# V_2.net
KiCad netlist of a schematic drawn in Altium Designer
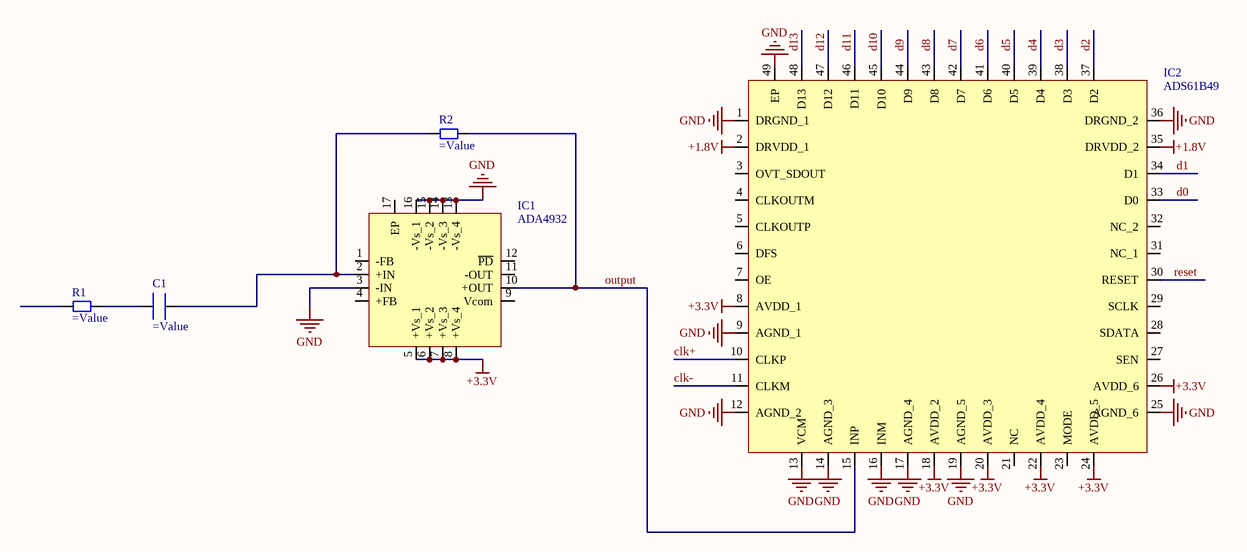
[diagram p0: V_2.SchDoc]

(export (version "E")
  (design (tool "Eeschema 10.0.6"))
  (components
    (comp (ref "C1") (value "~") (footprint "Copasitor") (libsource (lib "V_2") (part "Copasitor")))
    (comp (ref "IC1") (value "ADA4932") (footprint "ADA4932") (libsource (lib "V_2") (part "ADA4932")))
    (comp (ref "IC2") (value "ADS61B49") (footprint "ADS61B49") (libsource (lib "V_2") (part "ADS61B49")))
    (comp (ref "R1") (value "~") (footprint "Res") (libsource (lib "V_2") (part "Resistor")))
    (comp (ref "R2") (value "~") (footprint "Res") (libsource (lib "V_2") (part "Resistor")))
  )
  (nets
    (net (code "1") (name "+1.8V") (class "Default")
      (node (ref "IC2") (pin "2") (pinfunction "DRVDD_1_2") (pintype "passive"))
      (node (ref "IC2") (pin "35") (pinfunction "DRVDD_2_35") (pintype "passive"))
    )
    (net (code "2") (name "+3.3V") (class "Default")
      (node (ref "IC1") (pin "5") (pinfunction "+Vs_1_5") (pintype "passive"))
      (node (ref "IC1") (pin "6") (pinfunction "+Vs_2_6") (pintype "passive"))
      (node (ref "IC1") (pin "7") (pinfunction "+Vs_3_7") (pintype "passive"))
      (node (ref "IC1") (pin "8") (pinfunction "+Vs_4_8") (pintype "passive"))
      (node (ref "IC2") (pin "18") (pinfunction "AVDD_2_18") (pintype "passive"))
      (node (ref "IC2") (pin "20") (pinfunction "AVDD_3_20") (pintype "passive"))
      (node (ref "IC2") (pin "22") (pinfunction "AVDD_4_22") (pintype "passive"))
      (node (ref "IC2") (pin "24") (pinfunction "AVDD_5_24") (pintype "passive"))
      (node (ref "IC2") (pin "26") (pinfunction "AVDD_6_26") (pintype "passive"))
      (node (ref "IC2") (pin "8") (pinfunction "AVDD_1_8") (pintype "passive"))
    )
    (net (code "3") (name "/clk+") (class "Default")
      (node (ref "IC2") (pin "10") (pinfunction "CLKP_10") (pintype "passive"))
    )
    (net (code "4") (name "/clk-") (class "Default")
      (node (ref "IC2") (pin "11") (pinfunction "CLKM_11") (pintype "passive"))
    )
    (net (code "5") (name "/d0") (class "Default")
      (node (ref "IC2") (pin "33") (pinfunction "D0_33") (pintype "passive"))
    )
    (net (code "6") (name "/d1") (class "Default")
      (node (ref "IC2") (pin "34") (pinfunction "D1_34") (pintype "passive"))
    )
    (net (code "7") (name "/d2") (class "Default")
      (node (ref "IC2") (pin "37") (pinfunction "D2_37") (pintype "passive"))
    )
    (net (code "8") (name "/d3") (class "Default")
      (node (ref "IC2") (pin "38") (pinfunction "D3_38") (pintype "passive"))
    )
    (net (code "9") (name "/d4") (class "Default")
      (node (ref "IC2") (pin "39") (pinfunction "D4_39") (pintype "passive"))
    )
    (net (code "10") (name "/d5") (class "Default")
      (node (ref "IC2") (pin "40") (pinfunction "D5_40") (pintype "passive"))
    )
    (net (code "11") (name "/d6") (class "Default")
      (node (ref "IC2") (pin "41") (pinfunction "D6_41") (pintype "passive"))
    )
    (net (code "12") (name "/d7") (class "Default")
      (node (ref "IC2") (pin "42") (pinfunction "D7_42") (pintype "passive"))
    )
    (net (code "13") (name "/d8") (class "Default")
      (node (ref "IC2") (pin "43") (pinfunction "D8_43") (pintype "passive"))
    )
    (net (code "14") (name "/d9") (class "Default")
      (node (ref "IC2") (pin "44") (pinfunction "D9_44") (pintype "passive"))
    )
    (net (code "15") (name "/d10") (class "Default")
      (node (ref "IC2") (pin "45") (pinfunction "D10_45") (pintype "passive"))
    )
    (net (code "16") (name "/d11") (class "Default")
      (node (ref "IC2") (pin "46") (pinfunction "D11_46") (pintype "passive"))
    )
    (net (code "17") (name "/d12") (class "Default")
      (node (ref "IC2") (pin "47") (pinfunction "D12_47") (pintype "passive"))
    )
    (net (code "18") (name "/d13") (class "Default")
      (node (ref "IC2") (pin "48") (pinfunction "D13_48") (pintype "passive"))
    )
    (net (code "19") (name "/output") (class "Default")
      (node (ref "IC1") (pin "10") (pinfunction "+OUT_10") (pintype "passive"))
      (node (ref "IC2") (pin "15") (pinfunction "INP_15") (pintype "passive"))
      (node (ref "R2") (pin "1") (pintype "passive"))
    )
    (net (code "20") (name "/reset") (class "Default")
      (node (ref "IC2") (pin "30") (pinfunction "RESET_30") (pintype "passive"))
    )
    (net (code "21") (name "GND") (class "Default")
      (node (ref "IC1") (pin "13") (pinfunction "-Vs_4_13") (pintype "passive"))
      (node (ref "IC1") (pin "14") (pinfunction "-Vs_3_14") (pintype "passive"))
      (node (ref "IC1") (pin "15") (pinfunction "-Vs_2_15") (pintype "passive"))
      (node (ref "IC1") (pin "16") (pinfunction "-Vs_1_16") (pintype "passive"))
      (node (ref "IC1") (pin "3") (pinfunction "-IN_3") (pintype "passive"))
      (node (ref "IC2") (pin "1") (pinfunction "DRGND_1_1") (pintype "passive"))
      (node (ref "IC2") (pin "12") (pinfunction "AGND_2_12") (pintype "passive"))
      (node (ref "IC2") (pin "13") (pinfunction "VCM_13") (pintype "passive"))
      (node (ref "IC2") (pin "14") (pinfunction "AGND_3_14") (pintype "passive"))
      (node (ref "IC2") (pin "16") (pinfunction "INM_16") (pintype "passive"))
      (node (ref "IC2") (pin "17") (pinfunction "AGND_4_17") (pintype "passive"))
      (node (ref "IC2") (pin "19") (pinfunction "AGND_5_19") (pintype "passive"))
      (node (ref "IC2") (pin "25") (pinfunction "AGND_6_25") (pintype "passive"))
      (node (ref "IC2") (pin "36") (pinfunction "DRGND_2_36") (pintype "passive"))
      (node (ref "IC2") (pin "49") (pinfunction "EP_49") (pintype "passive"))
      (node (ref "IC2") (pin "9") (pinfunction "AGND_1_9") (pintype "passive"))
    )
    (net (code "22") (name "Net-(C1-Pad1)") (class "Default")
      (node (ref "C1") (pin "1") (pintype "passive"))
      (node (ref "R1") (pin "1") (pintype "passive"))
    )
    (net (code "23") (name "Net-(IC1-+IN)") (class "Default")
      (node (ref "C1") (pin "2") (pintype "passive"))
      (node (ref "IC1") (pin "2") (pinfunction "+IN_2") (pintype "passive"))
      (node (ref "R2") (pin "2") (pintype "passive"))
    )
    (net (code "24") (name "unconnected-(IC1-+FB-Pad4)") (class "Default")
      (node (ref "IC1") (pin "4") (pinfunction "+FB_4") (pintype "passive"))
    )
    (net (code "25") (name "unconnected-(IC1--FB-Pad1)") (class "Default")
      (node (ref "IC1") (pin "1") (pinfunction "-FB_1") (pintype "passive"))
    )
    (net (code "26") (name "unconnected-(IC1--OUT-Pad11)") (class "Default")
      (node (ref "IC1") (pin "11") (pinfunction "-OUT_11") (pintype "passive"))
    )
    (net (code "27") (name "unconnected-(IC1-EP-Pad17)") (class "Default")
      (node (ref "IC1") (pin "17") (pinfunction "EP_17") (pintype "passive"))
    )
    (net (code "28") (name "unconnected-(IC1-Vcom-Pad9)") (class "Default")
      (node (ref "IC1") (pin "9") (pinfunction "Vcom_9") (pintype "passive"))
    )
    (net (code "29") (name "unconnected-(IC1-~{PD}-Pad12)") (class "Default")
      (node (ref "IC1") (pin "12") (pinfunction "~{PD}_12") (pintype "passive"))
    )
    (net (code "30") (name "unconnected-(IC2-CLKOUTM-Pad4)") (class "Default")
      (node (ref "IC2") (pin "4") (pinfunction "CLKOUTM_4") (pintype "passive"))
    )
    (net (code "31") (name "unconnected-(IC2-CLKOUTP-Pad5)") (class "Default")
      (node (ref "IC2") (pin "5") (pinfunction "CLKOUTP_5") (pintype "passive"))
    )
    (net (code "32") (name "unconnected-(IC2-DFS-Pad6)") (class "Default")
      (node (ref "IC2") (pin "6") (pinfunction "DFS_6") (pintype "passive"))
    )
    (net (code "33") (name "unconnected-(IC2-MODE-Pad23)") (class "Default")
      (node (ref "IC2") (pin "23") (pinfunction "MODE_23") (pintype "passive"))
    )
    (net (code "34") (name "unconnected-(IC2-NC-Pad21)") (class "Default")
      (node (ref "IC2") (pin "21") (pinfunction "NC_21") (pintype "passive"))
    )
    (net (code "35") (name "unconnected-(IC2-NC_1-Pad31)") (class "Default")
      (node (ref "IC2") (pin "31") (pinfunction "NC_1_31") (pintype "passive"))
    )
    (net (code "36") (name "unconnected-(IC2-NC_2-Pad32)") (class "Default")
      (node (ref "IC2") (pin "32") (pinfunction "NC_2_32") (pintype "passive"))
    )
    (net (code "37") (name "unconnected-(IC2-OE-Pad7)") (class "Default")
      (node (ref "IC2") (pin "7") (pinfunction "OE_7") (pintype "passive"))
    )
    (net (code "38") (name "unconnected-(IC2-OVT_SDOUT-Pad3)") (class "Default")
      (node (ref "IC2") (pin "3") (pinfunction "OVT_SDOUT_3") (pintype "passive"))
    )
    (net (code "39") (name "unconnected-(IC2-SCLK-Pad29)") (class "Default")
      (node (ref "IC2") (pin "29") (pinfunction "SCLK_29") (pintype "passive"))
    )
    (net (code "40") (name "unconnected-(IC2-SDATA-Pad28)") (class "Default")
      (node (ref "IC2") (pin "28") (pinfunction "SDATA_28") (pintype "passive"))
    )
    (net (code "41") (name "unconnected-(IC2-SEN-Pad27)") (class "Default")
      (node (ref "IC2") (pin "27") (pinfunction "SEN_27") (pintype "passive"))
    )
    (net (code "42") (name "unconnected-(R1-Pad2)") (class "Default")
      (node (ref "R1") (pin "2") (pintype "passive"))
    )
  )
)
